# POWER.net
KiCad netlist of a schematic drawn in Altium Designer
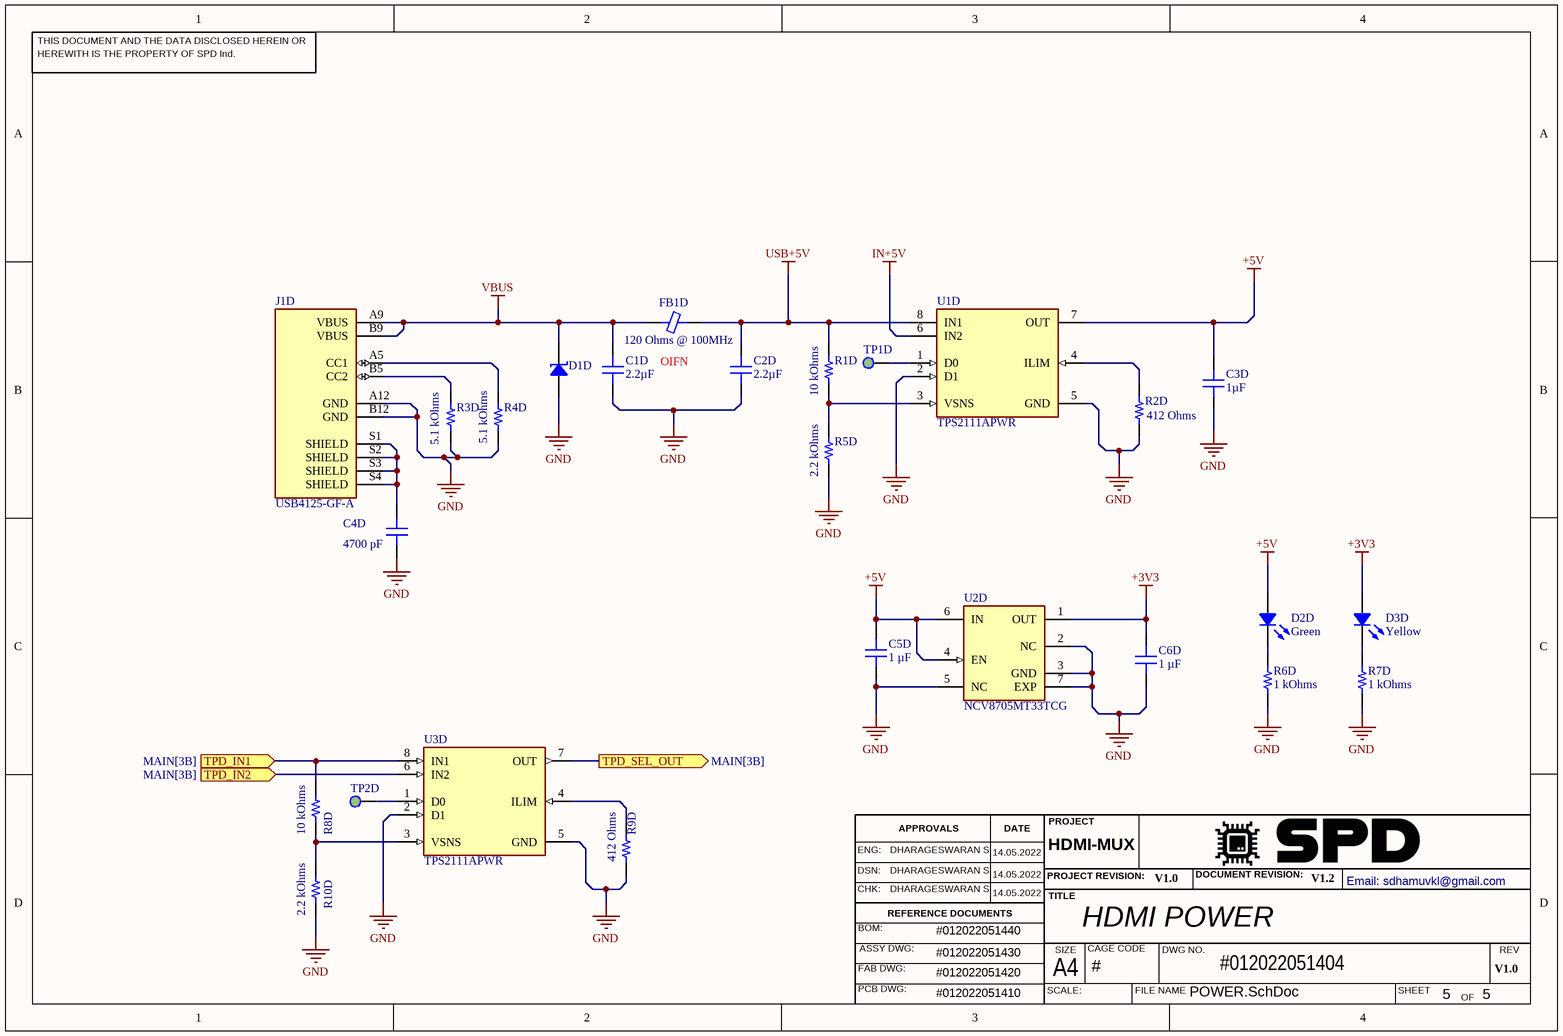
[diagram p0: POWER.SchDoc]

(export (version "E")
  (design (tool "Eeschema 10.0.6"))
  (components
    (comp (ref "C1D")
      (value "2.2µF")
      (footprint "CAP 0402_1005")
      (description "CAP CER 2.2UF 10V X5R 0402")
      (fields (field (name "PART NUMBER") "0402ZD225KAT2A") (field (name "MANUFACTURER") "AVX Corporation"))
      (libsource (lib "Postgres Altium Library - altium_library") (part "Capacitor"))
    )
    (comp (ref "C2D")
      (value "2.2µF")
      (footprint "CAP 0402_1005")
      (description "CAP CER 2.2UF 10V X5R 0402")
      (fields (field (name "PART NUMBER") "0402ZD225KAT2A") (field (name "MANUFACTURER") "AVX Corporation"))
      (libsource (lib "Postgres Altium Library - altium_library") (part "Capacitor"))
    )
    (comp (ref "C3D")
      (value "1µF")
      (footprint "CAP 0603_1608")
      (description "CAP CER 1UF 6.3V X5R 0603")
      (fields (field (name "PART NUMBER") "06036D105KAT2A") (field (name "MANUFACTURER") "AVX Corporation"))
      (libsource (lib "Postgres Altium Library - altium_library") (part "Capacitor"))
    )
    (comp (ref "C4D")
      (value "4700 pF")
      (footprint "CAP 0402_1005")
      (description "CAP CER 0402 4.7NF 16V X7R 10%")
      (fields (field (name "PART NUMBER") "C0402C472K4RECAUTO") (field (name "MANUFACTURER") "KEMET"))
      (libsource (lib "Postgres Altium Library - altium_library") (part "Capacitor"))
    )
    (comp (ref "C5D")
      (value "1 µF")
      (footprint "CAP 0402_1005")
      (description "CAP CER 1UF 16V X6S 0402")
      (fields
        (field (name "PART NUMBER") "GRM155C81C105KE11D")
        (field (name "MANUFACTURER") "Murata Electronics")
      )
      (libsource (lib "Postgres Altium Library - altium_library") (part "Capacitor"))
    )
    (comp (ref "C6D")
      (value "1 µF")
      (footprint "CAP 0402_1005")
      (description "CAP CER 1UF 16V X6S 0402")
      (fields
        (field (name "PART NUMBER") "GRM155C81C105KE11D")
        (field (name "MANUFACTURER") "Murata Electronics")
      )
      (libsource (lib "Postgres Altium Library - altium_library") (part "Capacitor"))
    )
    (comp (ref "D1D")
      (value "VTVS5V0ASMF-M3-08")
      (footprint "SMF DO-219AB")
      (description "TVS DIODE 5V 8.9V DO219AB")
      (fields (field (name "MANUFACTURER") "Vishay Semiconductor Diodes Division"))
      (libsource (lib "Postgres Altium Library - altium_library") (part "DIODE TVS UNI"))
    )
    (comp (ref "D2D")
      (value "Green")
      (footprint "LED 0402_1005 GREEN")
      (description "LED GREEN DIFFUSED 0402 SMD")
      (fields (field (name "PART NUMBER") "HSMG-C280") (field (name "MANUFACTURER") "Broadcom Limited"))
      (libsource (lib "Postgres Altium Library - altium_library") (part "LED"))
    )
    (comp (ref "D3D")
      (value "Yellow")
      (footprint "LED 0402_1005 YELLOW")
      (description "LED YELLOW CLEAR CHIP SMD")
      (fields (field (name "PART NUMBER") "XZMYK68W-2") (field (name "MANUFACTURER") "SunLED"))
      (libsource (lib "Postgres Altium Library - altium_library") (part "LED"))
    )
    (comp (ref "FB1D")
      (value "120 Ohms @ 100MHz")
      (footprint "FER 0201_0603")
      (description "FERRITE BEAD 120 OHM 0201 1LN")
      (fields (field (name "PART NUMBER") "BKP0603HM121-T") (field (name "MANUFACTURER") "Taiyo Yuden"))
      (libsource (lib "Postgres Altium Library - altium_library") (part "Ferrite Chip"))
    )
    (comp (ref "J1D")
      (value "USB4125-GF-A")
      (footprint "USB4125-GF-A")
      (description "CONN RCPT TYPE C 6P SMD RA")
      (fields (field (name "MP") "USB4125-GF-A_REVA2") (field (name "MANUFACTURER") "GCT"))
      (libsource (lib "Postgres Altium Library - altium_library") (part "USB 3.0 TYPE C 6PIN"))
    )
    (comp (ref "R1D")
      (value "10 kOhms")
      (footprint "RES 0402_1005")
      (description "RES SMD 10K OHM 1% 1/16W 0402")
      (fields (field (name "PART NUMBER") "AA0402FR-0710KL") (field (name "TOLERANCE") "±1%"))
      (libsource (lib "Postgres Altium Library - altium_library") (part "Resistor"))
    )
    (comp (ref "R2D")
      (value "412 Ohms")
      (footprint "RES 0402_1005")
      (description "RES SMD 412 OHM 1% 1/16W 0402")
      (fields (field (name "PART NUMBER") "CR0402-FX-4120GLF") (field (name "TOLERANCE") "±1%"))
      (libsource (lib "Postgres Altium Library - altium_library") (part "Resistor"))
    )
    (comp (ref "R3D")
      (value "5.1 kOhms")
      (footprint "RES 0402_1005")
      (description "RES SMD 5.1K OHM 1% 1/16W 0402")
      (fields (field (name "PART NUMBER") "AC0402FR-075K1L") (field (name "TOLERANCE") "±1%"))
      (libsource (lib "Postgres Altium Library - altium_library") (part "Resistor"))
    )
    (comp (ref "R4D")
      (value "5.1 kOhms")
      (footprint "RES 0402_1005")
      (description "RES SMD 5.1K OHM 1% 1/16W 0402")
      (fields (field (name "PART NUMBER") "AC0402FR-075K1L") (field (name "TOLERANCE") "±1%"))
      (libsource (lib "Postgres Altium Library - altium_library") (part "Resistor"))
    )
    (comp (ref "R5D")
      (value "2.2 kOhms")
      (footprint "RES 0402_1005")
      (description "RES SMD 2.2K OHM 5% 1/16W 0402")
      (fields (field (name "PART NUMBER") "AC0402JR-072K2L") (field (name "TOLERANCE") "±5%"))
      (libsource (lib "Postgres Altium Library - altium_library") (part "Resistor"))
    )
    (comp (ref "R6D")
      (value "1 kOhms")
      (footprint "RES 0402_1005")
      (description "RES SMD 1K OHM 1% 1/16W 0402")
      (fields (field (name "PART NUMBER") "AA0402FR-071KL") (field (name "TOLERANCE") "±1%"))
      (libsource (lib "Postgres Altium Library - altium_library") (part "Resistor"))
    )
    (comp (ref "R7D")
      (value "1 kOhms")
      (footprint "RES 0402_1005")
      (description "RES SMD 1K OHM 1% 1/16W 0402")
      (fields (field (name "PART NUMBER") "AA0402FR-071KL") (field (name "TOLERANCE") "±1%"))
      (libsource (lib "Postgres Altium Library - altium_library") (part "Resistor"))
    )
    (comp (ref "R8D")
      (value "10 kOhms")
      (footprint "RES 0402_1005")
      (description "RES SMD 10K OHM 1% 1/16W 0402")
      (fields (field (name "PART NUMBER") "AA0402FR-0710KL") (field (name "TOLERANCE") "±1%"))
      (libsource (lib "Postgres Altium Library - altium_library") (part "Resistor"))
    )
    (comp (ref "R9D")
      (value "412 Ohms")
      (footprint "RES 0402_1005")
      (description "RES SMD 412 OHM 1% 1/16W 0402")
      (fields (field (name "PART NUMBER") "CR0402-FX-4120GLF") (field (name "TOLERANCE") "±1%"))
      (libsource (lib "Postgres Altium Library - altium_library") (part "Resistor"))
    )
    (comp (ref "R10D")
      (value "2.2 kOhms")
      (footprint "RES 0402_1005")
      (description "RES SMD 2.2K OHM 5% 1/16W 0402")
      (fields (field (name "PART NUMBER") "AC0402JR-072K2L") (field (name "TOLERANCE") "±5%"))
      (libsource (lib "Postgres Altium Library - altium_library") (part "Resistor"))
    )
    (comp (ref "TP1D")
      (value "ROUND PAD 0.5MM")
      (footprint "ROUND PAD 0.5MM")
      (libsource (lib "TestPoints") (part "ROUND PAD 0.5MM"))
    )
    (comp (ref "TP2D")
      (value "ROUND PAD 0.5MM")
      (footprint "ROUND PAD 0.5MM")
      (libsource (lib "TestPoints") (part "ROUND PAD 0.5MM"))
    )
    (comp (ref "U1D")
      (value "TPS2111APWR")
      (footprint "FP-PW0008A-IPC_B")
      (description "IC OR CTRLR SRC SELECT 8TSSOP")
      (libsource (lib "Altium Content Vault") (part "9c87117e5857231c598c52e5d53c09c"))
    )
    (comp (ref "U2D")
      (value "NCV8705MT33TCG")
      (footprint "FP-511BR-MFG")
      (description "IC REG LINEAR 3.3V 500MA 6WDFN")
      (libsource (lib "Altium Content Vault") (part "bd4554aa8b863d4f54479690e93ad39"))
    )
    (comp (ref "U3D")
      (value "TPS2111APWR")
      (footprint "FP-PW0008A-IPC_B")
      (description "IC OR CTRLR SRC SELECT 8TSSOP")
      (libsource (lib "Altium Content Vault") (part "9c87117e5857231c598c52e5d53c09c"))
    )
  )
  (nets
    (net (code "1") (name "+3V3") (class "Default")
      (node (ref "C6D") (pin "2") (pinfunction "2_2") (pintype "passive"))
      (node (ref "D3D") (pin "1") (pinfunction "1_1") (pintype "passive"))
      (node (ref "U2D") (pin "1") (pinfunction "OUT_1") (pintype "power_in"))
    )
    (net (code "2") (name "+5V") (class "Default")
      (node (ref "C3D") (pin "2") (pinfunction "2_2") (pintype "passive"))
      (node (ref "C5D") (pin "2") (pinfunction "2_2") (pintype "passive"))
      (node (ref "D2D") (pin "1") (pinfunction "1_1") (pintype "passive"))
      (node (ref "U1D") (pin "7") (pinfunction "OUT_7") (pintype "output"))
      (node (ref "U2D") (pin "4") (pinfunction "EN_4") (pintype "input"))
      (node (ref "U2D") (pin "6") (pinfunction "IN_6") (pintype "power_in"))
    )
    (net (code "3") (name "/TPD_IN1") (class "Default")
      (node (ref "R8D") (pin "2") (pinfunction "2_2") (pintype "passive"))
      (node (ref "U3D") (pin "8") (pinfunction "IN1_8") (pintype "input"))
    )
    (net (code "4") (name "/TPD_IN2") (class "Default")
      (node (ref "U3D") (pin "6") (pinfunction "IN2_6") (pintype "input"))
    )
    (net (code "5") (name "/TPD_SEL_OUT") (class "Default")
      (node (ref "U3D") (pin "7") (pinfunction "OUT_7") (pintype "output"))
    )
    (net (code "6") (name "GND") (class "Default")
      (node (ref "C1D") (pin "1") (pinfunction "1_1") (pintype "passive"))
      (node (ref "C2D") (pin "1") (pinfunction "1_1") (pintype "passive"))
      (node (ref "C3D") (pin "1") (pinfunction "1_1") (pintype "passive"))
      (node (ref "C4D") (pin "1") (pinfunction "1_1") (pintype "passive"))
      (node (ref "C5D") (pin "1") (pinfunction "1_1") (pintype "passive"))
      (node (ref "C6D") (pin "1") (pinfunction "1_1") (pintype "passive"))
      (node (ref "D1D") (pin "1") (pinfunction "1_1") (pintype "passive"))
      (node (ref "J1D") (pin "A12") (pinfunction "GND_A12") (pintype "power_in"))
      (node (ref "J1D") (pin "B12") (pinfunction "GND_B12") (pintype "power_in"))
      (node (ref "R10D") (pin "1") (pinfunction "1_1") (pintype "passive"))
      (node (ref "R2D") (pin "1") (pinfunction "1_1") (pintype "passive"))
      (node (ref "R3D") (pin "1") (pinfunction "1_1") (pintype "passive"))
      (node (ref "R4D") (pin "1") (pinfunction "1_1") (pintype "passive"))
      (node (ref "R5D") (pin "1") (pinfunction "1_1") (pintype "passive"))
      (node (ref "R6D") (pin "1") (pinfunction "1_1") (pintype "passive"))
      (node (ref "R7D") (pin "1") (pinfunction "1_1") (pintype "passive"))
      (node (ref "R9D") (pin "1") (pinfunction "1_1") (pintype "passive"))
      (node (ref "U1D") (pin "2") (pinfunction "D1_2") (pintype "input"))
      (node (ref "U1D") (pin "5") (pinfunction "GND_5") (pintype "power_in"))
      (node (ref "U2D") (pin "2") (pinfunction "NC_2") (pintype "passive"))
      (node (ref "U2D") (pin "3") (pinfunction "GND_3") (pintype "power_in"))
      (node (ref "U2D") (pin "5") (pinfunction "NC_5") (pintype "passive"))
      (node (ref "U2D") (pin "7") (pinfunction "EXP_7") (pintype "power_in"))
      (node (ref "U3D") (pin "2") (pinfunction "D1_2") (pintype "input"))
      (node (ref "U3D") (pin "5") (pinfunction "GND_5") (pintype "power_in"))
    )
    (net (code "7") (name "IN+5V") (class "Default")
      (node (ref "U1D") (pin "6") (pinfunction "IN2_6") (pintype "input"))
    )
    (net (code "8") (name "Net-(C4D-Pad2)") (class "Default")
      (node (ref "C4D") (pin "2") (pinfunction "2_2") (pintype "passive"))
      (node (ref "J1D") (pin "S1") (pinfunction "SHIELD_S1") (pintype "passive"))
      (node (ref "J1D") (pin "S2") (pinfunction "SHIELD_S2") (pintype "passive"))
      (node (ref "J1D") (pin "S3") (pinfunction "SHIELD_S3") (pintype "passive"))
      (node (ref "J1D") (pin "S4") (pinfunction "SHIELD_S4") (pintype "passive"))
    )
    (net (code "9") (name "Net-(D2D-Pad2)") (class "Default")
      (node (ref "D2D") (pin "2") (pinfunction "2_2") (pintype "passive"))
      (node (ref "R6D") (pin "2") (pinfunction "2_2") (pintype "passive"))
    )
    (net (code "10") (name "Net-(D3D-Pad2)") (class "Default")
      (node (ref "D3D") (pin "2") (pinfunction "2_2") (pintype "passive"))
      (node (ref "R7D") (pin "2") (pinfunction "2_2") (pintype "passive"))
    )
    (net (code "11") (name "Net-(J1D-CC1)") (class "Default")
      (node (ref "J1D") (pin "A5") (pinfunction "CC1_A5") (pintype "bidirectional"))
      (node (ref "R4D") (pin "2") (pinfunction "2_2") (pintype "passive"))
    )
    (net (code "12") (name "Net-(J1D-CC2)") (class "Default")
      (node (ref "J1D") (pin "B5") (pinfunction "CC2_B5") (pintype "bidirectional"))
      (node (ref "R3D") (pin "2") (pinfunction "2_2") (pintype "passive"))
    )
    (net (code "13") (name "Net-(U1D-D0)") (class "Default")
      (node (ref "TP1D") (pin "1") (pinfunction "1_1") (pintype "passive"))
      (node (ref "U1D") (pin "1") (pinfunction "D0_1") (pintype "input"))
    )
    (net (code "14") (name "Net-(U1D-ILIM)") (class "Default")
      (node (ref "R2D") (pin "2") (pinfunction "2_2") (pintype "passive"))
      (node (ref "U1D") (pin "4") (pinfunction "ILIM_4") (pintype "input"))
    )
    (net (code "15") (name "Net-(U1D-VSNS)") (class "Default")
      (node (ref "R1D") (pin "1") (pinfunction "1_1") (pintype "passive"))
      (node (ref "R5D") (pin "2") (pinfunction "2_2") (pintype "passive"))
      (node (ref "U1D") (pin "3") (pinfunction "VSNS_3") (pintype "input"))
    )
    (net (code "16") (name "Net-(U3D-D0)") (class "Default")
      (node (ref "TP2D") (pin "1") (pinfunction "1_1") (pintype "passive"))
      (node (ref "U3D") (pin "1") (pinfunction "D0_1") (pintype "input"))
    )
    (net (code "17") (name "Net-(U3D-ILIM)") (class "Default")
      (node (ref "R9D") (pin "2") (pinfunction "2_2") (pintype "passive"))
      (node (ref "U3D") (pin "4") (pinfunction "ILIM_4") (pintype "input"))
    )
    (net (code "18") (name "Net-(U3D-VSNS)") (class "Default")
      (node (ref "R10D") (pin "2") (pinfunction "2_2") (pintype "passive"))
      (node (ref "R8D") (pin "1") (pinfunction "1_1") (pintype "passive"))
      (node (ref "U3D") (pin "3") (pinfunction "VSNS_3") (pintype "input"))
    )
    (net (code "19") (name "USB+5V") (class "Default")
      (node (ref "C2D") (pin "2") (pinfunction "2_2") (pintype "passive"))
      (node (ref "FB1D") (pin "2") (pinfunction "2_2") (pintype "passive"))
      (node (ref "R1D") (pin "2") (pinfunction "2_2") (pintype "passive"))
      (node (ref "U1D") (pin "8") (pinfunction "IN1_8") (pintype "input"))
    )
    (net (code "20") (name "VBUS") (class "Default")
      (node (ref "C1D") (pin "2") (pinfunction "2_2") (pintype "passive"))
      (node (ref "D1D") (pin "2") (pinfunction "2_2") (pintype "passive"))
      (node (ref "FB1D") (pin "1") (pinfunction "1_1") (pintype "passive"))
      (node (ref "J1D") (pin "A9") (pinfunction "VBUS_A9") (pintype "power_in"))
      (node (ref "J1D") (pin "B9") (pinfunction "VBUS_B9") (pintype "power_in"))
    )
  )
)
